# SCH_nRF24L01-Messenger_2025-01-26.net
KiCad netlist of a schematic drawn in EasyEDA
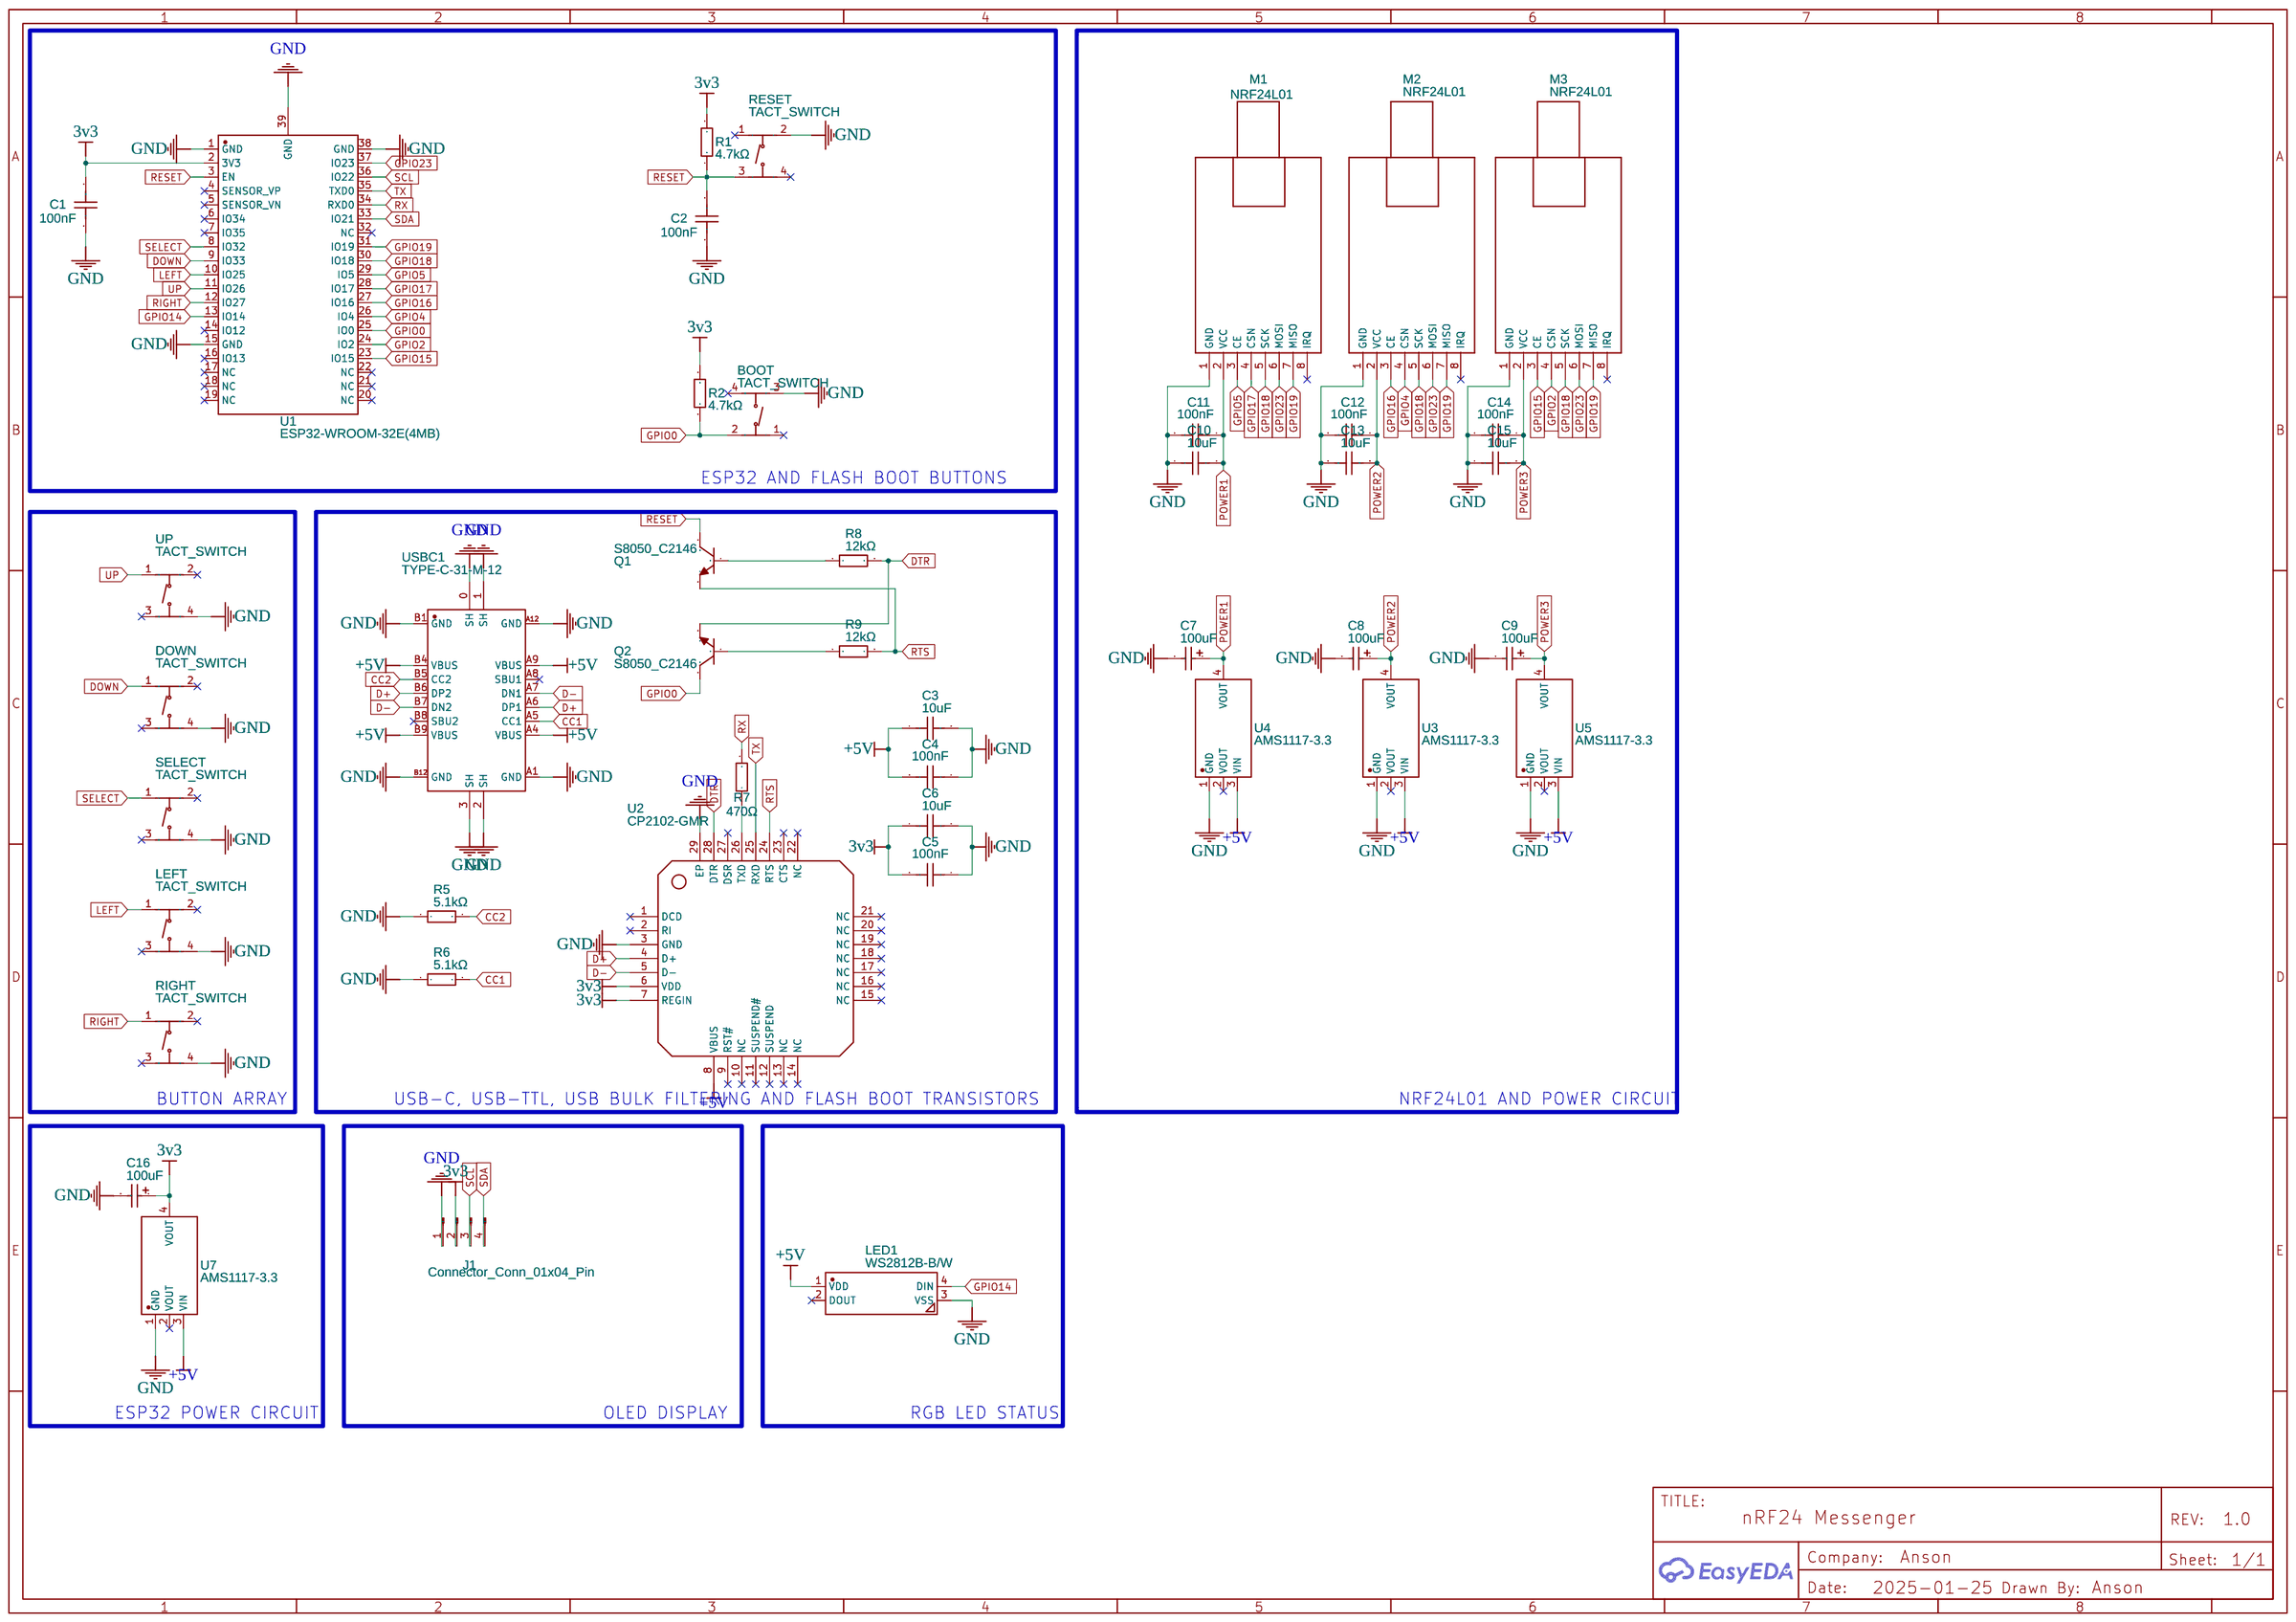
[diagram p0: schematic sheet]

(export (version "E")
  (design (tool "Eeschema 10.0.6"))
  (components
    (comp (ref "BOOT")
      (value "TACT_SWITCH")
      (fields
        (field (name "Manufacturer Part") "TS-1187A-B-A-B")
        (field (name "Manufacturer") "XKB Connectivity(中国星坤)")
      )
      (libsource (lib "") (part "TS-1187A-B-A-B_2"))
    )
    (comp (ref "C1")
      (value "100nF")
      (fields
        (field (name "Manufacturer Part") "CC0805KRX7R9BB104")
        (field (name "Manufacturer") "YAGEO(国巨)")
      )
      (libsource (lib "") (part "CC0805KRX7R9BB104"))
    )
    (comp (ref "C2")
      (value "100nF")
      (fields
        (field (name "Manufacturer Part") "CC0805KRX7R9BB104")
        (field (name "Manufacturer") "YAGEO(国巨)")
      )
      (libsource (lib "") (part "CC0805KRX7R9BB104"))
    )
    (comp (ref "C3")
      (value "10uF")
      (fields
        (field (name "Manufacturer Part") "CL21A106KAYNNNE")
        (field (name "Manufacturer") "SAMSUNG(三星)")
      )
      (libsource (lib "") (part "CL21A106KAYNNNE"))
    )
    (comp (ref "C4")
      (value "100nF")
      (fields
        (field (name "Manufacturer Part") "CC0805KRX7R9BB104")
        (field (name "Manufacturer") "YAGEO(国巨)")
      )
      (libsource (lib "") (part "CC0805KRX7R9BB104_1"))
    )
    (comp (ref "C5")
      (value "100nF")
      (fields
        (field (name "Manufacturer Part") "CC0805KRX7R9BB104")
        (field (name "Manufacturer") "YAGEO(国巨)")
      )
      (libsource (lib "") (part "CC0805KRX7R9BB104_1"))
    )
    (comp (ref "C6")
      (value "10uF")
      (fields
        (field (name "Manufacturer Part") "CL21A106KAYNNNE")
        (field (name "Manufacturer") "SAMSUNG(三星)")
      )
      (libsource (lib "") (part "CL21A106KAYNNNE"))
    )
    (comp (ref "C7")
      (value "100uF")
      (fields (field (name "Manufacturer Part") "TAJB107K006RNJ") (field (name "Manufacturer") "Kyocera AVX"))
      (libsource (lib "") (part "TAJB107K006RNJ"))
    )
    (comp (ref "C8")
      (value "100uF")
      (fields (field (name "Manufacturer Part") "TAJB107K006RNJ") (field (name "Manufacturer") "Kyocera AVX"))
      (libsource (lib "") (part "TAJB107K006RNJ"))
    )
    (comp (ref "C9")
      (value "100uF")
      (fields (field (name "Manufacturer Part") "TAJB107K006RNJ") (field (name "Manufacturer") "Kyocera AVX"))
      (libsource (lib "") (part "TAJB107K006RNJ"))
    )
    (comp (ref "C10")
      (value "10uF")
      (fields
        (field (name "Manufacturer Part") "CL21A106KAYNNNE")
        (field (name "Manufacturer") "SAMSUNG(三星)")
      )
      (libsource (lib "") (part "CL21A106KAYNNNE"))
    )
    (comp (ref "C11")
      (value "100nF")
      (fields
        (field (name "Manufacturer Part") "CC0805KRX7R9BB104")
        (field (name "Manufacturer") "YAGEO(国巨)")
      )
      (libsource (lib "") (part "CC0805KRX7R9BB104_1"))
    )
    (comp (ref "C12")
      (value "100nF")
      (fields
        (field (name "Manufacturer Part") "CC0805KRX7R9BB104")
        (field (name "Manufacturer") "YAGEO(国巨)")
      )
      (libsource (lib "") (part "CC0805KRX7R9BB104_1"))
    )
    (comp (ref "C13")
      (value "10uF")
      (fields
        (field (name "Manufacturer Part") "CL21A106KAYNNNE")
        (field (name "Manufacturer") "SAMSUNG(三星)")
      )
      (libsource (lib "") (part "CL21A106KAYNNNE"))
    )
    (comp (ref "C14")
      (value "100nF")
      (fields
        (field (name "Manufacturer Part") "CC0805KRX7R9BB104")
        (field (name "Manufacturer") "YAGEO(国巨)")
      )
      (libsource (lib "") (part "CC0805KRX7R9BB104_1"))
    )
    (comp (ref "C15")
      (value "10uF")
      (fields
        (field (name "Manufacturer Part") "CL21A106KAYNNNE")
        (field (name "Manufacturer") "SAMSUNG(三星)")
      )
      (libsource (lib "") (part "CL21A106KAYNNNE"))
    )
    (comp (ref "C16")
      (value "100uF")
      (fields (field (name "Manufacturer Part") "TAJB107K006RNJ") (field (name "Manufacturer") "Kyocera AVX"))
      (libsource (lib "") (part "TAJB107K006RNJ"))
    )
    (comp (ref "DOWN")
      (value "TACT_SWITCH")
      (fields
        (field (name "Manufacturer Part") "TS-1187A-B-A-B")
        (field (name "Manufacturer") "XKB Connectivity(中国星坤)")
      )
      (libsource (lib "") (part "TS-1187A-B-A-B"))
    )
    (comp (ref "J1")
      (value "Connector_Conn_01x04_Pin")
      (libsource (lib "") (part "Connector_Conn_01x04_Pin"))
    )
    (comp (ref "LED1")
      (value "WS2812B-B/W")
      (fields (field (name "Manufacturer Part") "WS2812B-B/T") (field (name "Manufacturer") "worldsemi"))
      (libsource (lib "") (part "WS2812B-B/W"))
    )
    (comp (ref "LEFT")
      (value "TACT_SWITCH")
      (fields
        (field (name "Manufacturer Part") "TS-1187A-B-A-B")
        (field (name "Manufacturer") "XKB Connectivity(中国星坤)")
      )
      (libsource (lib "") (part "TS-1187A-B-A-B_4"))
    )
    (comp (ref "M1") (value "NRF24L01") (libsource (lib "") (part "WIRELESS-NRF24L01-PA-EXT")))
    (comp (ref "M2") (value "NRF24L01") (libsource (lib "") (part "WIRELESS-NRF24L01-PA-EXT")))
    (comp (ref "M3") (value "NRF24L01") (libsource (lib "") (part "WIRELESS-NRF24L01-PA-EXT")))
    (comp (ref "Q1")
      (value "S8050_C2146")
      (fields
        (field (name "Manufacturer Part") "S8050 J3Y(RANGE:200-350)")
        (field (name "Manufacturer") "CJ(江苏长电/长晶)")
      )
      (libsource (lib "") (part "S8050_C2146_1"))
    )
    (comp (ref "Q2")
      (value "S8050_C2146")
      (fields
        (field (name "Manufacturer Part") "S8050 J3Y(RANGE:200-350)")
        (field (name "Manufacturer") "CJ(江苏长电/长晶)")
      )
      (libsource (lib "") (part "S8050_C2146"))
    )
    (comp (ref "R1")
      (value "4.7kΩ")
      (fields
        (field (name "Manufacturer Part") "0805W8F4701T5E")
        (field (name "Manufacturer") "UNI-ROYAL(厚声)")
      )
      (libsource (lib "") (part "0805W8F4701T5E"))
    )
    (comp (ref "R2")
      (value "4.7kΩ")
      (fields
        (field (name "Manufacturer Part") "0805W8F4701T5E")
        (field (name "Manufacturer") "UNI-ROYAL(厚声)")
      )
      (libsource (lib "") (part "0805W8F4701T5E"))
    )
    (comp (ref "R5")
      (value "5.1kΩ")
      (fields
        (field (name "Manufacturer Part") "0805W8F5101T5E")
        (field (name "Manufacturer") "UNI-ROYAL(厚声)")
      )
      (libsource (lib "") (part "0805W8F5101T5E"))
    )
    (comp (ref "R6")
      (value "5.1kΩ")
      (fields
        (field (name "Manufacturer Part") "0805W8F5101T5E")
        (field (name "Manufacturer") "UNI-ROYAL(厚声)")
      )
      (libsource (lib "") (part "0805W8F5101T5E"))
    )
    (comp (ref "R7")
      (value "470Ω")
      (fields
        (field (name "Manufacturer Part") "0805W8F4700T5E")
        (field (name "Manufacturer") "UNI-ROYAL(厚声)")
      )
      (libsource (lib "") (part "0805W8F4700T5E"))
    )
    (comp (ref "R8")
      (value "12kΩ")
      (fields
        (field (name "Manufacturer Part") "0805W8F1202T5E")
        (field (name "Manufacturer") "UNI-ROYAL(厚声)")
      )
      (libsource (lib "") (part "0805W8F1202T5E"))
    )
    (comp (ref "R9")
      (value "12kΩ")
      (fields
        (field (name "Manufacturer Part") "0805W8F1202T5E")
        (field (name "Manufacturer") "UNI-ROYAL(厚声)")
      )
      (libsource (lib "") (part "0805W8F1202T5E"))
    )
    (comp (ref "RESET")
      (value "TACT_SWITCH")
      (fields
        (field (name "Manufacturer Part") "TS-1187A-B-A-B")
        (field (name "Manufacturer") "XKB Connectivity(中国星坤)")
      )
      (libsource (lib "") (part "TS-1187A-B-A-B_1"))
    )
    (comp (ref "RIGHT")
      (value "TACT_SWITCH")
      (fields
        (field (name "Manufacturer Part") "TS-1187A-B-A-B")
        (field (name "Manufacturer") "XKB Connectivity(中国星坤)")
      )
      (libsource (lib "") (part "TS-1187A-B-A-B_6"))
    )
    (comp (ref "SELECT")
      (value "TACT_SWITCH")
      (fields
        (field (name "Manufacturer Part") "TS-1187A-B-A-B")
        (field (name "Manufacturer") "XKB Connectivity(中国星坤)")
      )
      (libsource (lib "") (part "TS-1187A-B-A-B_5"))
    )
    (comp (ref "U1")
      (value "ESP32-WROOM-32E(4MB)")
      (fields
        (field (name "Manufacturer Part") "ESP32-WROOM-32E-N4")
        (field (name "Manufacturer") "ESPRESSIF(乐鑫)")
      )
      (libsource (lib "") (part "ESP32-WROOM-32E(4MB)"))
    )
    (comp (ref "U2")
      (value "CP2102-GMR")
      (fields (field (name "Manufacturer") "SKYWORKS/SILICON LABS(芯科)"))
      (libsource (lib "") (part "CP2102-GMR"))
    )
    (comp (ref "U3")
      (value "AMS1117-3.3")
      (fields (field (name "Manufacturer") "AMS"))
      (libsource (lib "") (part "AMS1117-3.3"))
    )
    (comp (ref "U4")
      (value "AMS1117-3.3")
      (fields (field (name "Manufacturer") "AMS"))
      (libsource (lib "") (part "AMS1117-3.3"))
    )
    (comp (ref "U5")
      (value "AMS1117-3.3")
      (fields (field (name "Manufacturer") "AMS"))
      (libsource (lib "") (part "AMS1117-3.3"))
    )
    (comp (ref "U7")
      (value "AMS1117-3.3")
      (fields (field (name "Manufacturer") "AMS"))
      (libsource (lib "") (part "AMS1117-3.3"))
    )
    (comp (ref "UP")
      (value "TACT_SWITCH")
      (fields
        (field (name "Manufacturer Part") "TS-1187A-B-A-B")
        (field (name "Manufacturer") "XKB Connectivity(中国星坤)")
      )
      (libsource (lib "") (part "TS-1187A-B-A-B_3"))
    )
    (comp (ref "USBC1")
      (value "TYPE-C-31-M-12")
      (fields (field (name "Manufacturer") "韩国韩荣"))
      (libsource (lib "") (part "TYPE-C-31-M-12"))
    )
  )
  (nets
    (net (code "1") (name "+5V") (class "Default")
      (node (ref "C3") (pin "1") (pinfunction "1_1") (pintype "unspecified"))
      (node (ref "C4") (pin "2") (pinfunction "2_2") (pintype "unspecified"))
      (node (ref "LED1") (pin "1") (pinfunction "VDD_1") (pintype "unspecified"))
      (node (ref "U2") (pin "8") (pinfunction "VBUS_8") (pintype "unspecified"))
      (node (ref "U3") (pin "3") (pinfunction "VIN_3") (pintype "unspecified"))
      (node (ref "U4") (pin "3") (pinfunction "VIN_3") (pintype "unspecified"))
      (node (ref "U5") (pin "3") (pinfunction "VIN_3") (pintype "unspecified"))
      (node (ref "U7") (pin "3") (pinfunction "VIN_3") (pintype "unspecified"))
      (node (ref "USBC1") (pin "A4") (pinfunction "VBUS_A4") (pintype "unspecified"))
      (node (ref "USBC1") (pin "A9") (pinfunction "VBUS_A9") (pintype "unspecified"))
      (node (ref "USBC1") (pin "B4") (pinfunction "VBUS_B4") (pintype "unspecified"))
      (node (ref "USBC1") (pin "B9") (pinfunction "VBUS_B9") (pintype "unspecified"))
    )
    (net (code "2") (name "3v3") (class "Default")
      (node (ref "C1") (pin "2") (pinfunction "2_2") (pintype "unspecified"))
      (node (ref "C16") (pin "1") (pinfunction "1_1") (pintype "input"))
      (node (ref "C5") (pin "2") (pinfunction "2_2") (pintype "unspecified"))
      (node (ref "C6") (pin "1") (pinfunction "1_1") (pintype "unspecified"))
      (node (ref "J1") (pin "2") (pinfunction "Pin_2_2") (pintype "unspecified"))
      (node (ref "R1") (pin "2") (pinfunction "2_2") (pintype "input"))
      (node (ref "R2") (pin "2") (pinfunction "2_2") (pintype "input"))
      (node (ref "U1") (pin "2") (pinfunction "3V3_2") (pintype "unspecified"))
      (node (ref "U2") (pin "6") (pinfunction "VDD_6") (pintype "unspecified"))
      (node (ref "U2") (pin "7") (pinfunction "REGIN_7") (pintype "unspecified"))
      (node (ref "U7") (pin "4") (pinfunction "VOUT_4") (pintype "unspecified"))
    )
    (net (code "3") (name "CC1") (class "Default")
      (node (ref "R6") (pin "2") (pinfunction "2_2") (pintype "input"))
      (node (ref "USBC1") (pin "A5") (pinfunction "CC1_A5") (pintype "unspecified"))
    )
    (net (code "4") (name "CC2") (class "Default")
      (node (ref "R5") (pin "2") (pinfunction "2_2") (pintype "input"))
      (node (ref "USBC1") (pin "B5") (pinfunction "CC2_B5") (pintype "unspecified"))
    )
    (net (code "5") (name "D+") (class "Default")
      (node (ref "U2") (pin "4") (pinfunction "D+_4") (pintype "unspecified"))
      (node (ref "USBC1") (pin "A6") (pinfunction "DP1_A6") (pintype "unspecified"))
      (node (ref "USBC1") (pin "B6") (pinfunction "DP2_B6") (pintype "unspecified"))
    )
    (net (code "6") (name "D-") (class "Default")
      (node (ref "U2") (pin "5") (pinfunction "D-_5") (pintype "unspecified"))
      (node (ref "USBC1") (pin "A7") (pinfunction "DN1_A7") (pintype "unspecified"))
      (node (ref "USBC1") (pin "B7") (pinfunction "DN2_B7") (pintype "unspecified"))
    )
    (net (code "7") (name "DOWN") (class "Default")
      (node (ref "DOWN") (pin "1") (pinfunction "A_1") (pintype "unspecified"))
      (node (ref "U1") (pin "9") (pinfunction "IO33_9") (pintype "unspecified"))
    )
    (net (code "8") (name "DTR") (class "Default")
      (node (ref "Q2") (pin "2") (pinfunction "E_2") (pintype "unspecified"))
      (node (ref "R8") (pin "2") (pinfunction "2_2") (pintype "input"))
      (node (ref "U2") (pin "28") (pinfunction "DTR_28") (pintype "unspecified"))
    )
    (net (code "9") (name "GND") (class "Default")
      (node (ref "BOOT") (pin "3") (pinfunction "C_3") (pintype "unspecified"))
      (node (ref "C1") (pin "1") (pinfunction "1_1") (pintype "unspecified"))
      (node (ref "C10") (pin "1") (pinfunction "1_1") (pintype "unspecified"))
      (node (ref "C11") (pin "2") (pinfunction "2_2") (pintype "unspecified"))
      (node (ref "C12") (pin "2") (pinfunction "2_2") (pintype "unspecified"))
      (node (ref "C13") (pin "1") (pinfunction "1_1") (pintype "unspecified"))
      (node (ref "C14") (pin "2") (pinfunction "2_2") (pintype "unspecified"))
      (node (ref "C15") (pin "1") (pinfunction "1_1") (pintype "unspecified"))
      (node (ref "C16") (pin "2") (pinfunction "2_2") (pintype "input"))
      (node (ref "C2") (pin "1") (pinfunction "1_1") (pintype "unspecified"))
      (node (ref "C3") (pin "2") (pinfunction "2_2") (pintype "unspecified"))
      (node (ref "C4") (pin "1") (pinfunction "1_1") (pintype "unspecified"))
      (node (ref "C5") (pin "1") (pinfunction "1_1") (pintype "unspecified"))
      (node (ref "C6") (pin "2") (pinfunction "2_2") (pintype "unspecified"))
      (node (ref "C7") (pin "2") (pinfunction "2_2") (pintype "input"))
      (node (ref "C8") (pin "2") (pinfunction "2_2") (pintype "input"))
      (node (ref "C9") (pin "2") (pinfunction "2_2") (pintype "input"))
      (node (ref "DOWN") (pin "4") (pinfunction "D_4") (pintype "unspecified"))
      (node (ref "J1") (pin "1") (pinfunction "Pin_1_1") (pintype "unspecified"))
      (node (ref "LED1") (pin "3") (pinfunction "VSS_3") (pintype "unspecified"))
      (node (ref "LEFT") (pin "4") (pinfunction "D_4") (pintype "unspecified"))
      (node (ref "M1") (pin "1") (pinfunction "GND_1") (pintype "bidirectional"))
      (node (ref "M2") (pin "1") (pinfunction "GND_1") (pintype "bidirectional"))
      (node (ref "M3") (pin "1") (pinfunction "GND_1") (pintype "bidirectional"))
      (node (ref "R5") (pin "1") (pinfunction "1_1") (pintype "input"))
      (node (ref "R6") (pin "1") (pinfunction "1_1") (pintype "input"))
      (node (ref "RESET") (pin "2") (pinfunction "B_2") (pintype "unspecified"))
      (node (ref "RIGHT") (pin "4") (pinfunction "D_4") (pintype "unspecified"))
      (node (ref "SELECT") (pin "4") (pinfunction "D_4") (pintype "unspecified"))
      (node (ref "U1") (pin "1") (pinfunction "GND_1") (pintype "unspecified"))
      (node (ref "U1") (pin "15") (pinfunction "GND_15") (pintype "unspecified"))
      (node (ref "U1") (pin "38") (pinfunction "GND_38") (pintype "unspecified"))
      (node (ref "U1") (pin "39") (pinfunction "GND_39") (pintype "unspecified"))
      (node (ref "U2") (pin "29") (pinfunction "EP_29") (pintype "unspecified"))
      (node (ref "U2") (pin "3") (pinfunction "GND_3") (pintype "unspecified"))
      (node (ref "U3") (pin "1") (pinfunction "GND_1") (pintype "unspecified"))
      (node (ref "U4") (pin "1") (pinfunction "GND_1") (pintype "unspecified"))
      (node (ref "U5") (pin "1") (pinfunction "GND_1") (pintype "unspecified"))
      (node (ref "U7") (pin "1") (pinfunction "GND_1") (pintype "unspecified"))
      (node (ref "UP") (pin "4") (pinfunction "D_4") (pintype "unspecified"))
      (node (ref "USBC1") (pin "0") (pinfunction "SH_0") (pintype "unspecified"))
      (node (ref "USBC1") (pin "1") (pinfunction "SH_1") (pintype "unspecified"))
      (node (ref "USBC1") (pin "2") (pinfunction "SH_2") (pintype "unspecified"))
      (node (ref "USBC1") (pin "3") (pinfunction "SH_3") (pintype "unspecified"))
      (node (ref "USBC1") (pin "A1") (pinfunction "GND_A1") (pintype "unspecified"))
      (node (ref "USBC1") (pin "A12") (pinfunction "GND_A12") (pintype "unspecified"))
      (node (ref "USBC1") (pin "B1") (pinfunction "GND_B1") (pintype "unspecified"))
      (node (ref "USBC1") (pin "B12") (pinfunction "GND_B12") (pintype "unspecified"))
    )
    (net (code "10") (name "GPIO0") (class "Default")
      (node (ref "BOOT") (pin "2") (pinfunction "B_2") (pintype "unspecified"))
      (node (ref "Q2") (pin "3") (pinfunction "C_3") (pintype "unspecified"))
      (node (ref "R2") (pin "1") (pinfunction "1_1") (pintype "input"))
      (node (ref "U1") (pin "25") (pinfunction "IO0_25") (pintype "unspecified"))
    )
    (net (code "11") (name "GPIO2") (class "Default")
      (node (ref "M3") (pin "4") (pinfunction "CSN_4") (pintype "bidirectional"))
      (node (ref "U1") (pin "24") (pinfunction "IO2_24") (pintype "unspecified"))
    )
    (net (code "12") (name "GPIO4") (class "Default")
      (node (ref "M2") (pin "4") (pinfunction "CSN_4") (pintype "bidirectional"))
      (node (ref "U1") (pin "26") (pinfunction "IO4_26") (pintype "unspecified"))
    )
    (net (code "13") (name "GPIO5") (class "Default")
      (node (ref "M1") (pin "3") (pinfunction "CE_3") (pintype "bidirectional"))
      (node (ref "U1") (pin "29") (pinfunction "IO5_29") (pintype "unspecified"))
    )
    (net (code "14") (name "GPIO14") (class "Default")
      (node (ref "LED1") (pin "4") (pinfunction "DIN_4") (pintype "unspecified"))
      (node (ref "U1") (pin "13") (pinfunction "IO14_13") (pintype "unspecified"))
    )
    (net (code "15") (name "GPIO15") (class "Default")
      (node (ref "M3") (pin "3") (pinfunction "CE_3") (pintype "bidirectional"))
      (node (ref "U1") (pin "23") (pinfunction "IO15_23") (pintype "unspecified"))
    )
    (net (code "16") (name "GPIO16") (class "Default")
      (node (ref "M2") (pin "3") (pinfunction "CE_3") (pintype "bidirectional"))
      (node (ref "U1") (pin "27") (pinfunction "IO16_27") (pintype "unspecified"))
    )
    (net (code "17") (name "GPIO17") (class "Default")
      (node (ref "M1") (pin "4") (pinfunction "CSN_4") (pintype "bidirectional"))
      (node (ref "U1") (pin "28") (pinfunction "IO17_28") (pintype "unspecified"))
    )
    (net (code "18") (name "GPIO18") (class "Default")
      (node (ref "M1") (pin "5") (pinfunction "SCK_5") (pintype "bidirectional"))
      (node (ref "M2") (pin "5") (pinfunction "SCK_5") (pintype "bidirectional"))
      (node (ref "M3") (pin "5") (pinfunction "SCK_5") (pintype "bidirectional"))
      (node (ref "U1") (pin "30") (pinfunction "IO18_30") (pintype "unspecified"))
    )
    (net (code "19") (name "GPIO19") (class "Default")
      (node (ref "M1") (pin "7") (pinfunction "MISO_7") (pintype "bidirectional"))
      (node (ref "M2") (pin "7") (pinfunction "MISO_7") (pintype "bidirectional"))
      (node (ref "M3") (pin "7") (pinfunction "MISO_7") (pintype "bidirectional"))
      (node (ref "U1") (pin "31") (pinfunction "IO19_31") (pintype "unspecified"))
    )
    (net (code "20") (name "GPIO23") (class "Default")
      (node (ref "M1") (pin "6") (pinfunction "MOSI_6") (pintype "bidirectional"))
      (node (ref "M2") (pin "6") (pinfunction "MOSI_6") (pintype "bidirectional"))
      (node (ref "M3") (pin "6") (pinfunction "MOSI_6") (pintype "bidirectional"))
      (node (ref "U1") (pin "37") (pinfunction "IO23_37") (pintype "unspecified"))
    )
    (net (code "21") (name "LEFT") (class "Default")
      (node (ref "LEFT") (pin "1") (pinfunction "A_1") (pintype "unspecified"))
      (node (ref "U1") (pin "10") (pinfunction "IO25_10") (pintype "unspecified"))
    )
    (net (code "22") (name "Net-(Q1-B)") (class "Default")
      (node (ref "Q1") (pin "1") (pinfunction "B_1") (pintype "unspecified"))
      (node (ref "R8") (pin "1") (pinfunction "1_1") (pintype "input"))
    )
    (net (code "23") (name "Net-(Q2-B)") (class "Default")
      (node (ref "Q2") (pin "1") (pinfunction "B_1") (pintype "unspecified"))
      (node (ref "R9") (pin "1") (pinfunction "1_1") (pintype "input"))
    )
    (net (code "24") (name "Net-(U2-TXD)") (class "Default")
      (node (ref "R7") (pin "1") (pinfunction "1_1") (pintype "input"))
      (node (ref "U2") (pin "26") (pinfunction "TXD_26") (pintype "unspecified"))
    )
    (net (code "25") (name "POWER1") (class "Default")
      (node (ref "C10") (pin "2") (pinfunction "2_2") (pintype "unspecified"))
      (node (ref "C11") (pin "1") (pinfunction "1_1") (pintype "unspecified"))
      (node (ref "C7") (pin "1") (pinfunction "1_1") (pintype "input"))
      (node (ref "M1") (pin "2") (pinfunction "VCC_2") (pintype "bidirectional"))
      (node (ref "U4") (pin "4") (pinfunction "VOUT_4") (pintype "unspecified"))
    )
    (net (code "26") (name "POWER2") (class "Default")
      (node (ref "C12") (pin "1") (pinfunction "1_1") (pintype "unspecified"))
      (node (ref "C13") (pin "2") (pinfunction "2_2") (pintype "unspecified"))
      (node (ref "C8") (pin "1") (pinfunction "1_1") (pintype "input"))
      (node (ref "M2") (pin "2") (pinfunction "VCC_2") (pintype "bidirectional"))
      (node (ref "U3") (pin "4") (pinfunction "VOUT_4") (pintype "unspecified"))
    )
    (net (code "27") (name "POWER3") (class "Default")
      (node (ref "C14") (pin "1") (pinfunction "1_1") (pintype "unspecified"))
      (node (ref "C15") (pin "2") (pinfunction "2_2") (pintype "unspecified"))
      (node (ref "C9") (pin "1") (pinfunction "1_1") (pintype "input"))
      (node (ref "M3") (pin "2") (pinfunction "VCC_2") (pintype "bidirectional"))
      (node (ref "U5") (pin "4") (pinfunction "VOUT_4") (pintype "unspecified"))
    )
    (net (code "28") (name "RESET") (class "Default")
      (node (ref "C2") (pin "2") (pinfunction "2_2") (pintype "unspecified"))
      (node (ref "Q1") (pin "3") (pinfunction "C_3") (pintype "unspecified"))
      (node (ref "R1") (pin "1") (pinfunction "1_1") (pintype "input"))
      (node (ref "RESET") (pin "3") (pinfunction "C_3") (pintype "unspecified"))
      (node (ref "U1") (pin "3") (pinfunction "EN_3") (pintype "unspecified"))
    )
    (net (code "29") (name "RIGHT") (class "Default")
      (node (ref "RIGHT") (pin "1") (pinfunction "A_1") (pintype "unspecified"))
      (node (ref "U1") (pin "12") (pinfunction "IO27_12") (pintype "unspecified"))
    )
    (net (code "30") (name "RTS") (class "Default")
      (node (ref "Q1") (pin "2") (pinfunction "E_2") (pintype "unspecified"))
      (node (ref "R9") (pin "2") (pinfunction "2_2") (pintype "input"))
      (node (ref "U2") (pin "24") (pinfunction "RTS_24") (pintype "unspecified"))
    )
    (net (code "31") (name "RX") (class "Default")
      (node (ref "R7") (pin "2") (pinfunction "2_2") (pintype "input"))
      (node (ref "U1") (pin "34") (pinfunction "RXD0_34") (pintype "unspecified"))
    )
    (net (code "32") (name "SCL") (class "Default")
      (node (ref "J1") (pin "3") (pinfunction "Pin_3_3") (pintype "unspecified"))
      (node (ref "U1") (pin "36") (pinfunction "IO22_36") (pintype "unspecified"))
    )
    (net (code "33") (name "SDA") (class "Default")
      (node (ref "J1") (pin "4") (pinfunction "Pin_4_4") (pintype "unspecified"))
      (node (ref "U1") (pin "33") (pinfunction "IO21_33") (pintype "unspecified"))
    )
    (net (code "34") (name "SELECT") (class "Default")
      (node (ref "SELECT") (pin "1") (pinfunction "A_1") (pintype "unspecified"))
      (node (ref "U1") (pin "8") (pinfunction "IO32_8") (pintype "unspecified"))
    )
    (net (code "35") (name "TX") (class "Default")
      (node (ref "U1") (pin "35") (pinfunction "TXD0_35") (pintype "unspecified"))
      (node (ref "U2") (pin "25") (pinfunction "RXD_25") (pintype "unspecified"))
    )
    (net (code "36") (name "UP") (class "Default")
      (node (ref "U1") (pin "11") (pinfunction "IO26_11") (pintype "unspecified"))
      (node (ref "UP") (pin "1") (pinfunction "A_1") (pintype "unspecified"))
    )
    (net (code "37") (name "unconnected-(BOOT-A-Pad1)") (class "Default")
      (node (ref "BOOT") (pin "1") (pinfunction "A_1") (pintype "unspecified+no_connect"))
    )
    (net (code "38") (name "unconnected-(BOOT-D-Pad4)") (class "Default")
      (node (ref "BOOT") (pin "4") (pinfunction "D_4") (pintype "unspecified+no_connect"))
    )
    (net (code "39") (name "unconnected-(DOWN-B-Pad2)") (class "Default")
      (node (ref "DOWN") (pin "2") (pinfunction "B_2") (pintype "unspecified+no_connect"))
    )
    (net (code "40") (name "unconnected-(DOWN-C-Pad3)") (class "Default")
      (node (ref "DOWN") (pin "3") (pinfunction "C_3") (pintype "unspecified+no_connect"))
    )
    (net (code "41") (name "unconnected-(LED1-DOUT-Pad2)") (class "Default")
      (node (ref "LED1") (pin "2") (pinfunction "DOUT_2") (pintype "unspecified+no_connect"))
    )
    (net (code "42") (name "unconnected-(LEFT-B-Pad2)") (class "Default")
      (node (ref "LEFT") (pin "2") (pinfunction "B_2") (pintype "unspecified+no_connect"))
    )
    (net (code "43") (name "unconnected-(LEFT-C-Pad3)") (class "Default")
      (node (ref "LEFT") (pin "3") (pinfunction "C_3") (pintype "unspecified+no_connect"))
    )
    (net (code "44") (name "unconnected-(M1-IRQ-Pad8)") (class "Default")
      (node (ref "M1") (pin "8") (pinfunction "IRQ_8") (pintype "bidirectional+no_connect"))
    )
    (net (code "45") (name "unconnected-(M2-IRQ-Pad8)") (class "Default")
      (node (ref "M2") (pin "8") (pinfunction "IRQ_8") (pintype "bidirectional+no_connect"))
    )
    (net (code "46") (name "unconnected-(M3-IRQ-Pad8)") (class "Default")
      (node (ref "M3") (pin "8") (pinfunction "IRQ_8") (pintype "bidirectional+no_connect"))
    )
    (net (code "47") (name "unconnected-(RESET-A-Pad1)") (class "Default")
      (node (ref "RESET") (pin "1") (pinfunction "A_1") (pintype "unspecified+no_connect"))
    )
    (net (code "48") (name "unconnected-(RESET-D-Pad4)") (class "Default")
      (node (ref "RESET") (pin "4") (pinfunction "D_4") (pintype "unspecified+no_connect"))
    )
    (net (code "49") (name "unconnected-(RIGHT-B-Pad2)") (class "Default")
      (node (ref "RIGHT") (pin "2") (pinfunction "B_2") (pintype "unspecified+no_connect"))
    )
    (net (code "50") (name "unconnected-(RIGHT-C-Pad3)") (class "Default")
      (node (ref "RIGHT") (pin "3") (pinfunction "C_3") (pintype "unspecified+no_connect"))
    )
    (net (code "51") (name "unconnected-(SELECT-B-Pad2)") (class "Default")
      (node (ref "SELECT") (pin "2") (pinfunction "B_2") (pintype "unspecified+no_connect"))
    )
    (net (code "52") (name "unconnected-(SELECT-C-Pad3)") (class "Default")
      (node (ref "SELECT") (pin "3") (pinfunction "C_3") (pintype "unspecified+no_connect"))
    )
    (net (code "53") (name "unconnected-(U1-IO12-Pad14)") (class "Default")
      (node (ref "U1") (pin "14") (pinfunction "IO12_14") (pintype "unspecified+no_connect"))
    )
    (net (code "54") (name "unconnected-(U1-IO13-Pad16)") (class "Default")
      (node (ref "U1") (pin "16") (pinfunction "IO13_16") (pintype "unspecified+no_connect"))
    )
    (net (code "55") (name "unconnected-(U1-IO34-Pad6)") (class "Default")
      (node (ref "U1") (pin "6") (pinfunction "IO34_6") (pintype "unspecified+no_connect"))
    )
    (net (code "56") (name "unconnected-(U1-IO35-Pad7)") (class "Default")
      (node (ref "U1") (pin "7") (pinfunction "IO35_7") (pintype "unspecified+no_connect"))
    )
    (net (code "57") (name "unconnected-(U1-NC-Pad17)") (class "Default")
      (node (ref "U1") (pin "17") (pinfunction "NC_17") (pintype "unspecified+no_connect"))
    )
    (net (code "58") (name "unconnected-(U1-NC-Pad18)") (class "Default")
      (node (ref "U1") (pin "18") (pinfunction "NC_18") (pintype "unspecified+no_connect"))
    )
    (net (code "59") (name "unconnected-(U1-NC-Pad19)") (class "Default")
      (node (ref "U1") (pin "19") (pinfunction "NC_19") (pintype "unspecified+no_connect"))
    )
    (net (code "60") (name "unconnected-(U1-NC-Pad20)") (class "Default")
      (node (ref "U1") (pin "20") (pinfunction "NC_20") (pintype "unspecified+no_connect"))
    )
    (net (code "61") (name "unconnected-(U1-NC-Pad21)") (class "Default")
      (node (ref "U1") (pin "21") (pinfunction "NC_21") (pintype "unspecified+no_connect"))
    )
    (net (code "62") (name "unconnected-(U1-NC-Pad22)") (class "Default")
      (node (ref "U1") (pin "22") (pinfunction "NC_22") (pintype "unspecified+no_connect"))
    )
    (net (code "63") (name "unconnected-(U1-NC-Pad32)") (class "Default")
      (node (ref "U1") (pin "32") (pinfunction "NC_32") (pintype "unspecified+no_connect"))
    )
    (net (code "64") (name "unconnected-(U1-SENSOR_VN-Pad5)") (class "Default")
      (node (ref "U1") (pin "5") (pinfunction "SENSOR_VN_5") (pintype "unspecified+no_connect"))
    )
    (net (code "65") (name "unconnected-(U1-SENSOR_VP-Pad4)") (class "Default")
      (node (ref "U1") (pin "4") (pinfunction "SENSOR_VP_4") (pintype "unspecified+no_connect"))
    )
    (net (code "66") (name "unconnected-(U2-CTS-Pad23)") (class "Default")
      (node (ref "U2") (pin "23") (pinfunction "CTS_23") (pintype "unspecified+no_connect"))
    )
    (net (code "67") (name "unconnected-(U2-DCD-Pad1)") (class "Default")
      (node (ref "U2") (pin "1") (pinfunction "DCD_1") (pintype "unspecified+no_connect"))
    )
    (net (code "68") (name "unconnected-(U2-DSR-Pad27)") (class "Default")
      (node (ref "U2") (pin "27") (pinfunction "DSR_27") (pintype "unspecified+no_connect"))
    )
    (net (code "69") (name "unconnected-(U2-NC-Pad10)") (class "Default")
      (node (ref "U2") (pin "10") (pinfunction "NC_10") (pintype "unspecified+no_connect"))
    )
    (net (code "70") (name "unconnected-(U2-NC-Pad13)") (class "Default")
      (node (ref "U2") (pin "13") (pinfunction "NC_13") (pintype "unspecified+no_connect"))
    )
    (net (code "71") (name "unconnected-(U2-NC-Pad14)") (class "Default")
      (node (ref "U2") (pin "14") (pinfunction "NC_14") (pintype "unspecified+no_connect"))
    )
    (net (code "72") (name "unconnected-(U2-NC-Pad15)") (class "Default")
      (node (ref "U2") (pin "15") (pinfunction "NC_15") (pintype "unspecified+no_connect"))
    )
    (net (code "73") (name "unconnected-(U2-NC-Pad16)") (class "Default")
      (node (ref "U2") (pin "16") (pinfunction "NC_16") (pintype "unspecified+no_connect"))
    )
    (net (code "74") (name "unconnected-(U2-NC-Pad17)") (class "Default")
      (node (ref "U2") (pin "17") (pinfunction "NC_17") (pintype "unspecified+no_connect"))
    )
    (net (code "75") (name "unconnected-(U2-NC-Pad18)") (class "Default")
      (node (ref "U2") (pin "18") (pinfunction "NC_18") (pintype "unspecified+no_connect"))
    )
    (net (code "76") (name "unconnected-(U2-NC-Pad19)") (class "Default")
      (node (ref "U2") (pin "19") (pinfunction "NC_19") (pintype "unspecified+no_connect"))
    )
    (net (code "77") (name "unconnected-(U2-NC-Pad20)") (class "Default")
      (node (ref "U2") (pin "20") (pinfunction "NC_20") (pintype "unspecified+no_connect"))
    )
    (net (code "78") (name "unconnected-(U2-NC-Pad21)") (class "Default")
      (node (ref "U2") (pin "21") (pinfunction "NC_21") (pintype "unspecified+no_connect"))
    )
    (net (code "79") (name "unconnected-(U2-NC-Pad22)") (class "Default")
      (node (ref "U2") (pin "22") (pinfunction "NC_22") (pintype "unspecified+no_connect"))
    )
    (net (code "80") (name "unconnected-(U2-RI-Pad2)") (class "Default")
      (node (ref "U2") (pin "2") (pinfunction "RI_2") (pintype "unspecified+no_connect"))
    )
    (net (code "81") (name "unconnected-(U2-RST#-Pad9)") (class "Default")
      (node (ref "U2") (pin "9") (pinfunction "RST#_9") (pintype "unspecified+no_connect"))
    )
    (net (code "82") (name "unconnected-(U2-SUSPEND#-Pad11)") (class "Default")
      (node (ref "U2") (pin "11") (pinfunction "SUSPEND#_11") (pintype "unspecified+no_connect"))
    )
    (net (code "83") (name "unconnected-(U2-SUSPEND-Pad12)") (class "Default")
      (node (ref "U2") (pin "12") (pinfunction "SUSPEND_12") (pintype "unspecified+no_connect"))
    )
    (net (code "84") (name "unconnected-(U3-VOUT-Pad2)") (class "Default")
      (node (ref "U3") (pin "2") (pinfunction "VOUT_2") (pintype "unspecified+no_connect"))
    )
    (net (code "85") (name "unconnected-(U4-VOUT-Pad2)") (class "Default")
      (node (ref "U4") (pin "2") (pinfunction "VOUT_2") (pintype "unspecified+no_connect"))
    )
    (net (code "86") (name "unconnected-(U5-VOUT-Pad2)") (class "Default")
      (node (ref "U5") (pin "2") (pinfunction "VOUT_2") (pintype "unspecified+no_connect"))
    )
    (net (code "87") (name "unconnected-(U7-VOUT-Pad2)") (class "Default")
      (node (ref "U7") (pin "2") (pinfunction "VOUT_2") (pintype "unspecified+no_connect"))
    )
    (net (code "88") (name "unconnected-(UP-B-Pad2)") (class "Default")
      (node (ref "UP") (pin "2") (pinfunction "B_2") (pintype "unspecified+no_connect"))
    )
    (net (code "89") (name "unconnected-(UP-C-Pad3)") (class "Default")
      (node (ref "UP") (pin "3") (pinfunction "C_3") (pintype "unspecified+no_connect"))
    )
    (net (code "90") (name "unconnected-(USBC1-SBU1-PadA8)") (class "Default")
      (node (ref "USBC1") (pin "A8") (pinfunction "SBU1_A8") (pintype "unspecified+no_connect"))
    )
    (net (code "91") (name "unconnected-(USBC1-SBU2-PadB8)") (class "Default")
      (node (ref "USBC1") (pin "B8") (pinfunction "SBU2_B8") (pintype "unspecified+no_connect"))
    )
  )
)
